# hbridge_v3.net
KiCad netlist of a schematic drawn in EAGLE
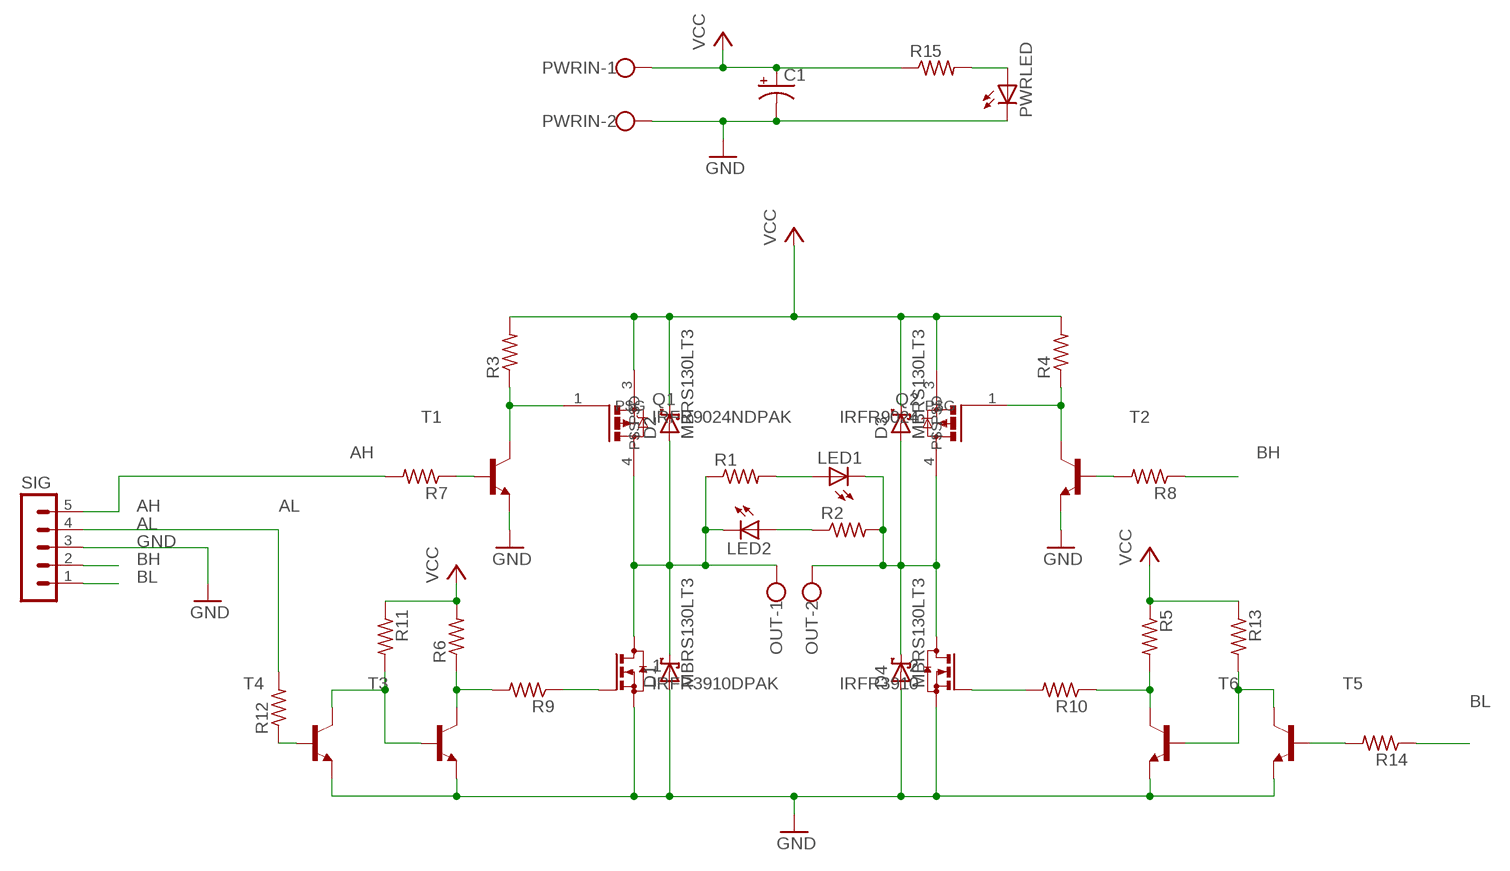
[diagram p0: schematic, sheet 1]

(export (version "E")
  (design (tool "Eeschema 10.0.6"))
  (components
    (comp (ref "1")
      (value "IRFR3910DPAK")
      (footprint "eagle-import:D-PAK_TO252AA")
      (libsource (lib "eagle-import") (part "IRFR3910DPAK"))
    )
    (comp (ref "2")
      (value "IRFR3910")
      (footprint "eagle-import:D-PAK_TO252AA")
      (libsource (lib "eagle-import") (part "IRFR3910DPAK"))
    )
    (comp (ref "C1")
      (value "CPOL-USE5-10.5")
      (footprint "eagle-import:E5-10,5")
      (libsource (lib "eagle-import") (part "CPOL-USE5-10.5"))
    )
    (comp (ref "D1")
      (value "MBRS130LT3")
      (footprint "eagle-import:SMB")
      (libsource (lib "eagle-import") (part "MBRS130LT3"))
    )
    (comp (ref "D2")
      (value "MBRS130LT3")
      (footprint "eagle-import:SMB")
      (libsource (lib "eagle-import") (part "MBRS130LT3"))
    )
    (comp (ref "D3")
      (value "MBRS130LT3")
      (footprint "eagle-import:SMB")
      (libsource (lib "eagle-import") (part "MBRS130LT3"))
    )
    (comp (ref "D4")
      (value "MBRS130LT3")
      (footprint "eagle-import:SMB")
      (libsource (lib "eagle-import") (part "MBRS130LT3"))
    )
    (comp (ref "LED1")
      (value "LEDCHIP-LED0805")
      (footprint "eagle-import:CHIP-LED0805")
      (libsource (lib "eagle-import") (part "LEDCHIP-LED0805"))
    )
    (comp (ref "LED2")
      (value "LEDCHIP-LED0805")
      (footprint "eagle-import:CHIP-LED0805")
      (libsource (lib "eagle-import") (part "LEDCHIP-LED0805"))
    )
    (comp (ref "OUT")
      (value "W237-102")
      (footprint "eagle-import:W237-102")
      (fields (field (name "MPN") "237-102"))
      (libsource (lib "eagle-import") (part "W237-102"))
    )
    (comp (ref "PWRIN")
      (value "W237-102")
      (footprint "eagle-import:W237-102")
      (fields
        (field (name "MPN") "237-102")
        (field (name "MPN_1") "237-102")
        (field (name "OC_FARNELL") "unknown")
        (field (name "OC_NEWARK") "70K9898")
      )
      (libsource (lib "eagle-import") (part "W237-102"))
    )
    (comp (ref "PWRLED")
      (value "LEDCHIP-LED0805")
      (footprint "eagle-import:CHIP-LED0805")
      (libsource (lib "eagle-import") (part "LEDCHIP-LED0805"))
    )
    (comp (ref "Q1")
      (value "IRFR9024NDPAK")
      (footprint "eagle-import:D-PAK_TO252AA")
      (libsource (lib "eagle-import") (part "IRFR9024NDPAK"))
    )
    (comp (ref "Q2")
      (value "IRFR9024")
      (footprint "eagle-import:D-PAK_TO252AA")
      (libsource (lib "eagle-import") (part "IRFR9024NDPAK"))
    )
    (comp (ref "R1")
      (value "R-US_R0805")
      (footprint "eagle-import:R0805")
      (libsource (lib "eagle-import") (part "R-US_R0805"))
    )
    (comp (ref "R2")
      (value "R-US_R0805")
      (footprint "eagle-import:R0805")
      (libsource (lib "eagle-import") (part "R-US_R0805"))
    )
    (comp (ref "R3")
      (value "R-US_R0805")
      (footprint "eagle-import:R0805")
      (libsource (lib "eagle-import") (part "R-US_R0805"))
    )
    (comp (ref "R4")
      (value "R-US_R0805")
      (footprint "eagle-import:R0805")
      (libsource (lib "eagle-import") (part "R-US_R0805"))
    )
    (comp (ref "R5")
      (value "R-US_R0805")
      (footprint "eagle-import:R0805")
      (libsource (lib "eagle-import") (part "R-US_R0805"))
    )
    (comp (ref "R6")
      (value "R-US_R0805")
      (footprint "eagle-import:R0805")
      (libsource (lib "eagle-import") (part "R-US_R0805"))
    )
    (comp (ref "R7")
      (value "R-US_R0805")
      (footprint "eagle-import:R0805")
      (libsource (lib "eagle-import") (part "R-US_R0805"))
    )
    (comp (ref "R8")
      (value "R-US_R0805")
      (footprint "eagle-import:R0805")
      (libsource (lib "eagle-import") (part "R-US_R0805"))
    )
    (comp (ref "R9")
      (value "R-US_R0805")
      (footprint "eagle-import:R0805")
      (libsource (lib "eagle-import") (part "R-US_R0805"))
    )
    (comp (ref "R10")
      (value "R-US_R0805")
      (footprint "eagle-import:R0805")
      (libsource (lib "eagle-import") (part "R-US_R0805"))
    )
    (comp (ref "R11")
      (value "R-US_R0805")
      (footprint "eagle-import:R0805")
      (libsource (lib "eagle-import") (part "R-US_R0805"))
    )
    (comp (ref "R12")
      (value "R-US_R0805")
      (footprint "eagle-import:R0805")
      (libsource (lib "eagle-import") (part "R-US_R0805"))
    )
    (comp (ref "R13")
      (value "R-US_R0805")
      (footprint "eagle-import:R0805")
      (libsource (lib "eagle-import") (part "R-US_R0805"))
    )
    (comp (ref "R14")
      (value "R-US_R0805")
      (footprint "eagle-import:R0805")
      (libsource (lib "eagle-import") (part "R-US_R0805"))
    )
    (comp (ref "R15")
      (value "R-US_R0805")
      (footprint "eagle-import:R0805")
      (libsource (lib "eagle-import") (part "R-US_R0805"))
    )
    (comp (ref "SIG")
      (value "MA05-1")
      (footprint "eagle-import:MA05-1")
      (libsource (lib "eagle-import") (part "MA05-1"))
    )
    (comp (ref "T1")
      (value "MMBT2222ALT1-NPN-SOT23-BEC")
      (footprint "eagle-import:SOT23-BEC")
      (libsource (lib "eagle-import") (part "-NPN-SOT23-BECMMBT2222ALT1"))
    )
    (comp (ref "T2")
      (value "MMBT2222ALT1-NPN-SOT23-BEC")
      (footprint "eagle-import:SOT23-BEC")
      (libsource (lib "eagle-import") (part "-NPN-SOT23-BECMMBT2222ALT1"))
    )
    (comp (ref "T3")
      (value "MMBT2222ALT1-NPN-SOT23-BEC")
      (footprint "eagle-import:SOT23-BEC")
      (libsource (lib "eagle-import") (part "-NPN-SOT23-BECMMBT2222ALT1"))
    )
    (comp (ref "T4")
      (value "MMBT2222ALT1-NPN-SOT23-BEC")
      (footprint "eagle-import:SOT23-BEC")
      (libsource (lib "eagle-import") (part "-NPN-SOT23-BECMMBT2222ALT1"))
    )
    (comp (ref "T5")
      (value "MMBT2222ALT1-NPN-SOT23-BEC")
      (footprint "eagle-import:SOT23-BEC")
      (libsource (lib "eagle-import") (part "-NPN-SOT23-BECMMBT2222ALT1"))
    )
    (comp (ref "T6")
      (value "MMBT2222ALT1-NPN-SOT23-BEC")
      (footprint "eagle-import:SOT23-BEC")
      (libsource (lib "eagle-import") (part "-NPN-SOT23-BECMMBT2222ALT1"))
    )
  )
  (nets
    (net (code "1") (name "/AH") (class "Default")
      (node (ref "R7") (pin "2") (pinfunction "2_2") (pintype "passive"))
      (node (ref "SIG") (pin "5") (pinfunction "5_5") (pintype "passive"))
    )
    (net (code "2") (name "/AL") (class "Default")
      (node (ref "R12") (pin "2") (pinfunction "2_2") (pintype "passive"))
      (node (ref "SIG") (pin "4") (pinfunction "4_4") (pintype "passive"))
    )
    (net (code "3") (name "/BH") (class "Default")
      (node (ref "R8") (pin "1") (pinfunction "1_1") (pintype "passive"))
      (node (ref "SIG") (pin "2") (pinfunction "2_2") (pintype "passive"))
    )
    (net (code "4") (name "/BL") (class "Default")
      (node (ref "R14") (pin "1") (pinfunction "1_1") (pintype "passive"))
      (node (ref "SIG") (pin "1") (pinfunction "1_1") (pintype "passive"))
    )
    (net (code "5") (name "GND") (class "Default")
      (node (ref "1") (pin "3") (pinfunction "S_3") (pintype "passive"))
      (node (ref "2") (pin "3") (pinfunction "S_3") (pintype "passive"))
      (node (ref "C1") (pin "-") (pinfunction "-_-") (pintype "passive"))
      (node (ref "D1") (pin "A") (pinfunction "A_A") (pintype "passive"))
      (node (ref "D4") (pin "A") (pinfunction "A_A") (pintype "passive"))
      (node (ref "PWRIN") (pin "2") (pinfunction "KL_2") (pintype "passive"))
      (node (ref "PWRLED") (pin "C") (pinfunction "C_C") (pintype "passive"))
      (node (ref "SIG") (pin "3") (pinfunction "3_3") (pintype "passive"))
      (node (ref "T1") (pin "E") (pinfunction "E_E") (pintype "passive"))
      (node (ref "T2") (pin "E") (pinfunction "E_E") (pintype "passive"))
      (node (ref "T3") (pin "E") (pinfunction "E_E") (pintype "passive"))
      (node (ref "T4") (pin "E") (pinfunction "E_E") (pintype "passive"))
      (node (ref "T5") (pin "E") (pinfunction "E_E") (pintype "passive"))
      (node (ref "T6") (pin "E") (pinfunction "E_E") (pintype "passive"))
    )
    (net (code "6") (name "Net-(1-D)") (class "Default")
      (node (ref "1") (pin "4") (pinfunction "D_4") (pintype "passive"))
      (node (ref "D1") (pin "C") (pinfunction "C_C") (pintype "passive"))
      (node (ref "D2") (pin "A") (pinfunction "A_A") (pintype "passive"))
      (node (ref "LED2") (pin "C") (pinfunction "C_C") (pintype "passive"))
      (node (ref "OUT") (pin "1") (pinfunction "KL_1") (pintype "passive"))
      (node (ref "Q1") (pin "4") (pinfunction "P$D_4") (pintype "bidirectional"))
      (node (ref "R1") (pin "1") (pinfunction "1_1") (pintype "passive"))
    )
    (net (code "7") (name "Net-(1-G)") (class "Default")
      (node (ref "1") (pin "1") (pinfunction "G_1") (pintype "passive"))
      (node (ref "R9") (pin "1") (pinfunction "1_1") (pintype "passive"))
    )
    (net (code "8") (name "Net-(2-D)") (class "Default")
      (node (ref "2") (pin "4") (pinfunction "D_4") (pintype "passive"))
      (node (ref "D3") (pin "A") (pinfunction "A_A") (pintype "passive"))
      (node (ref "D4") (pin "C") (pinfunction "C_C") (pintype "passive"))
      (node (ref "LED1") (pin "C") (pinfunction "C_C") (pintype "passive"))
      (node (ref "OUT") (pin "2") (pinfunction "KL_2") (pintype "passive"))
      (node (ref "Q2") (pin "4") (pinfunction "P$D_4") (pintype "bidirectional"))
      (node (ref "R2") (pin "2") (pinfunction "2_2") (pintype "passive"))
    )
    (net (code "9") (name "Net-(2-G)") (class "Default")
      (node (ref "2") (pin "1") (pinfunction "G_1") (pintype "passive"))
      (node (ref "R10") (pin "2") (pinfunction "2_2") (pintype "passive"))
    )
    (net (code "10") (name "Net-(LED1-PadA)") (class "Default")
      (node (ref "LED1") (pin "A") (pinfunction "A_A") (pintype "passive"))
      (node (ref "R1") (pin "2") (pinfunction "2_2") (pintype "passive"))
    )
    (net (code "11") (name "Net-(LED2-PadA)") (class "Default")
      (node (ref "LED2") (pin "A") (pinfunction "A_A") (pintype "passive"))
      (node (ref "R2") (pin "1") (pinfunction "1_1") (pintype "passive"))
    )
    (net (code "12") (name "Net-(PWRLED-PadA)") (class "Default")
      (node (ref "PWRLED") (pin "A") (pinfunction "A_A") (pintype "passive"))
      (node (ref "R15") (pin "2") (pinfunction "2_2") (pintype "passive"))
    )
    (net (code "13") (name "Net-(Q1-P$G)") (class "Default")
      (node (ref "Q1") (pin "1") (pinfunction "P$G_1") (pintype "bidirectional"))
      (node (ref "R3") (pin "1") (pinfunction "1_1") (pintype "passive"))
      (node (ref "T1") (pin "C") (pinfunction "C_C") (pintype "passive"))
    )
    (net (code "14") (name "Net-(Q2-P$G)") (class "Default")
      (node (ref "Q2") (pin "1") (pinfunction "P$G_1") (pintype "bidirectional"))
      (node (ref "R4") (pin "1") (pinfunction "1_1") (pintype "passive"))
      (node (ref "T2") (pin "C") (pinfunction "C_C") (pintype "passive"))
    )
    (net (code "15") (name "Net-(R6-Pad1)") (class "Default")
      (node (ref "R6") (pin "1") (pinfunction "1_1") (pintype "passive"))
      (node (ref "R9") (pin "2") (pinfunction "2_2") (pintype "passive"))
      (node (ref "T3") (pin "C") (pinfunction "C_C") (pintype "passive"))
    )
    (net (code "16") (name "Net-(R7-Pad1)") (class "Default")
      (node (ref "R7") (pin "1") (pinfunction "1_1") (pintype "passive"))
      (node (ref "T1") (pin "B") (pinfunction "B_B") (pintype "passive"))
    )
    (net (code "17") (name "Net-(R8-Pad2)") (class "Default")
      (node (ref "R8") (pin "2") (pinfunction "2_2") (pintype "passive"))
      (node (ref "T2") (pin "B") (pinfunction "B_B") (pintype "passive"))
    )
    (net (code "18") (name "Net-(R10-Pad1)") (class "Default")
      (node (ref "R10") (pin "1") (pinfunction "1_1") (pintype "passive"))
      (node (ref "R5") (pin "2") (pinfunction "2_2") (pintype "passive"))
      (node (ref "T6") (pin "C") (pinfunction "C_C") (pintype "passive"))
    )
    (net (code "19") (name "Net-(R11-Pad2)") (class "Default")
      (node (ref "R11") (pin "2") (pinfunction "2_2") (pintype "passive"))
      (node (ref "T3") (pin "B") (pinfunction "B_B") (pintype "passive"))
      (node (ref "T4") (pin "C") (pinfunction "C_C") (pintype "passive"))
    )
    (net (code "20") (name "Net-(R12-Pad1)") (class "Default")
      (node (ref "R12") (pin "1") (pinfunction "1_1") (pintype "passive"))
      (node (ref "T4") (pin "B") (pinfunction "B_B") (pintype "passive"))
    )
    (net (code "21") (name "Net-(R13-Pad2)") (class "Default")
      (node (ref "R13") (pin "2") (pinfunction "2_2") (pintype "passive"))
      (node (ref "T5") (pin "C") (pinfunction "C_C") (pintype "passive"))
      (node (ref "T6") (pin "B") (pinfunction "B_B") (pintype "passive"))
    )
    (net (code "22") (name "Net-(R14-Pad2)") (class "Default")
      (node (ref "R14") (pin "2") (pinfunction "2_2") (pintype "passive"))
      (node (ref "T5") (pin "B") (pinfunction "B_B") (pintype "passive"))
    )
    (net (code "23") (name "VCC") (class "Default")
      (node (ref "C1") (pin "+") (pinfunction "+_+") (pintype "passive"))
      (node (ref "D2") (pin "C") (pinfunction "C_C") (pintype "passive"))
      (node (ref "D3") (pin "C") (pinfunction "C_C") (pintype "passive"))
      (node (ref "PWRIN") (pin "1") (pinfunction "KL_1") (pintype "passive"))
      (node (ref "Q1") (pin "3") (pinfunction "P$S_3") (pintype "bidirectional"))
      (node (ref "Q2") (pin "3") (pinfunction "P$S_3") (pintype "bidirectional"))
      (node (ref "R11") (pin "1") (pinfunction "1_1") (pintype "passive"))
      (node (ref "R13") (pin "1") (pinfunction "1_1") (pintype "passive"))
      (node (ref "R15") (pin "1") (pinfunction "1_1") (pintype "passive"))
      (node (ref "R3") (pin "2") (pinfunction "2_2") (pintype "passive"))
      (node (ref "R4") (pin "2") (pinfunction "2_2") (pintype "passive"))
      (node (ref "R5") (pin "1") (pinfunction "1_1") (pintype "passive"))
      (node (ref "R6") (pin "2") (pinfunction "2_2") (pintype "passive"))
    )
  )
)
